# Sheet6.net
KiCad netlist of a schematic drawn in Altium Designer
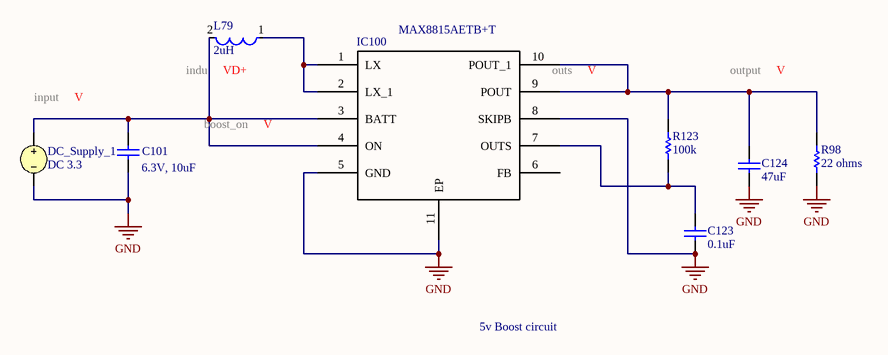
[diagram p0: Sheet6.SchDoc]

(export (version "E")
  (design (tool "Eeschema 10.0.6"))
  (components
    (comp (ref "C101")
      (value "6.3V, 10uF")
      (footprint "WCAP-CSGP_0603_L1.6W0.8H0.8_Reflow")
      (fields (field (name "TOLERANCE") "20%"))
      (libsource (lib "Altium Content Vault") (part "Capacitor_Non-Polarized"))
    )
    (comp (ref "C123")
      (value "0.1uF")
      (description "Capacitor")
      (libsource (lib "Simulation Generic Components") (part "Capacitor"))
    )
    (comp (ref "C124")
      (value "47uF")
      (footprint "CAPC1206(3216)190_N")
      (description "CAP 22uF 10V ±20% 1206 (3216 Metric) Thickness 1.9mm SMD")
      (fields (field (name "TOLERANCE") "Â±20%"))
      (libsource (lib "Altium Content Vault") (part "CAP"))
    )
    (comp (ref "DC_Supply_1")
      (value "DC 3.3")
      (description "Voltage Source")
      (fields (field (name "PUBLISHER") "Altium Limited"))
      (libsource (lib "Simulation Generic Components") (part "VSRC"))
    )
    (comp (ref "IC100")
      (value "MAX8815AETB+T")
      (footprint "21-0137I_T1033+2_MXM")
      (libsource (lib "Schlib1") (part "MAX8815AETB+T"))
    )
    (comp (ref "L79")
      (value "2uH")
      (footprint "FP-NR8040-H_4_2-MFG")
      (description "Shielded Wirewound Inductor 2uH 30% 7.6A 11.7mΩ SMD")
      (fields (field (name "TOLERANCE") "30%"))
      (libsource (lib "Altium Content Vault") (part "725321dda6339637d4d059423bc1c3c"))
    )
    (comp (ref "R98")
      (value "22 ohms")
      (description "Resistor")
      (libsource (lib "Simulation Generic Components") (part "Resistor"))
    )
    (comp (ref "R123")
      (value "100k")
      (description "Resistor")
      (libsource (lib "Simulation Generic Components") (part "Resistor"))
    )
  )
  (nets
    (net (code "1") (name "GND") (class "Default")
      (node (ref "C101") (pin "1") (pinfunction "1_1") (pintype "passive"))
      (node (ref "C123") (pin "1") (pinfunction "1_1") (pintype "passive"))
      (node (ref "C124") (pin "1") (pinfunction "1_1") (pintype "passive"))
      (node (ref "DC_Supply_1") (pin "2") (pinfunction "2_2") (pintype "passive"))
      (node (ref "IC100") (pin "11") (pinfunction "EP_11") (pintype "passive"))
      (node (ref "IC100") (pin "5") (pinfunction "GND_5") (pintype "passive"))
      (node (ref "IC100") (pin "8") (pinfunction "SKIPB_8") (pintype "passive"))
      (node (ref "R98") (pin "1") (pinfunction "1_1") (pintype "passive"))
    )
    (net (code "2") (name "Net-(IC100-BATT)") (class "Default")
      (node (ref "C101") (pin "2") (pinfunction "2_2") (pintype "passive"))
      (node (ref "DC_Supply_1") (pin "1") (pinfunction "1_1") (pintype "passive"))
      (node (ref "IC100") (pin "3") (pinfunction "BATT_3") (pintype "passive"))
      (node (ref "IC100") (pin "4") (pinfunction "ON_4") (pintype "passive"))
      (node (ref "L79") (pin "2") (pinfunction "2_2") (pintype "passive"))
    )
    (net (code "3") (name "Net-(IC100-LX)") (class "Default")
      (node (ref "IC100") (pin "1") (pinfunction "LX_1") (pintype "passive"))
      (node (ref "IC100") (pin "2") (pinfunction "LX_1_2") (pintype "passive"))
      (node (ref "L79") (pin "1") (pinfunction "1_1") (pintype "passive"))
    )
    (net (code "4") (name "Net-(IC100-OUTS)") (class "Default")
      (node (ref "C123") (pin "2") (pinfunction "2_2") (pintype "passive"))
      (node (ref "IC100") (pin "7") (pinfunction "OUTS_7") (pintype "passive"))
      (node (ref "R123") (pin "2") (pinfunction "2_2") (pintype "passive"))
    )
    (net (code "5") (name "Net-(IC100-POUT)") (class "Default")
      (node (ref "C124") (pin "2") (pinfunction "2_2") (pintype "passive"))
      (node (ref "IC100") (pin "10") (pinfunction "POUT_1_10") (pintype "passive"))
      (node (ref "IC100") (pin "9") (pinfunction "POUT_9") (pintype "passive"))
      (node (ref "R123") (pin "1") (pinfunction "1_1") (pintype "passive"))
      (node (ref "R98") (pin "2") (pinfunction "2_2") (pintype "passive"))
    )
    (net (code "6") (name "unconnected-(IC100-FB-Pad6)") (class "Default")
      (node (ref "IC100") (pin "6") (pinfunction "FB_6") (pintype "passive"))
    )
  )
)
